# Power_2019_2.net
KiCad netlist of a schematic drawn in EAGLE
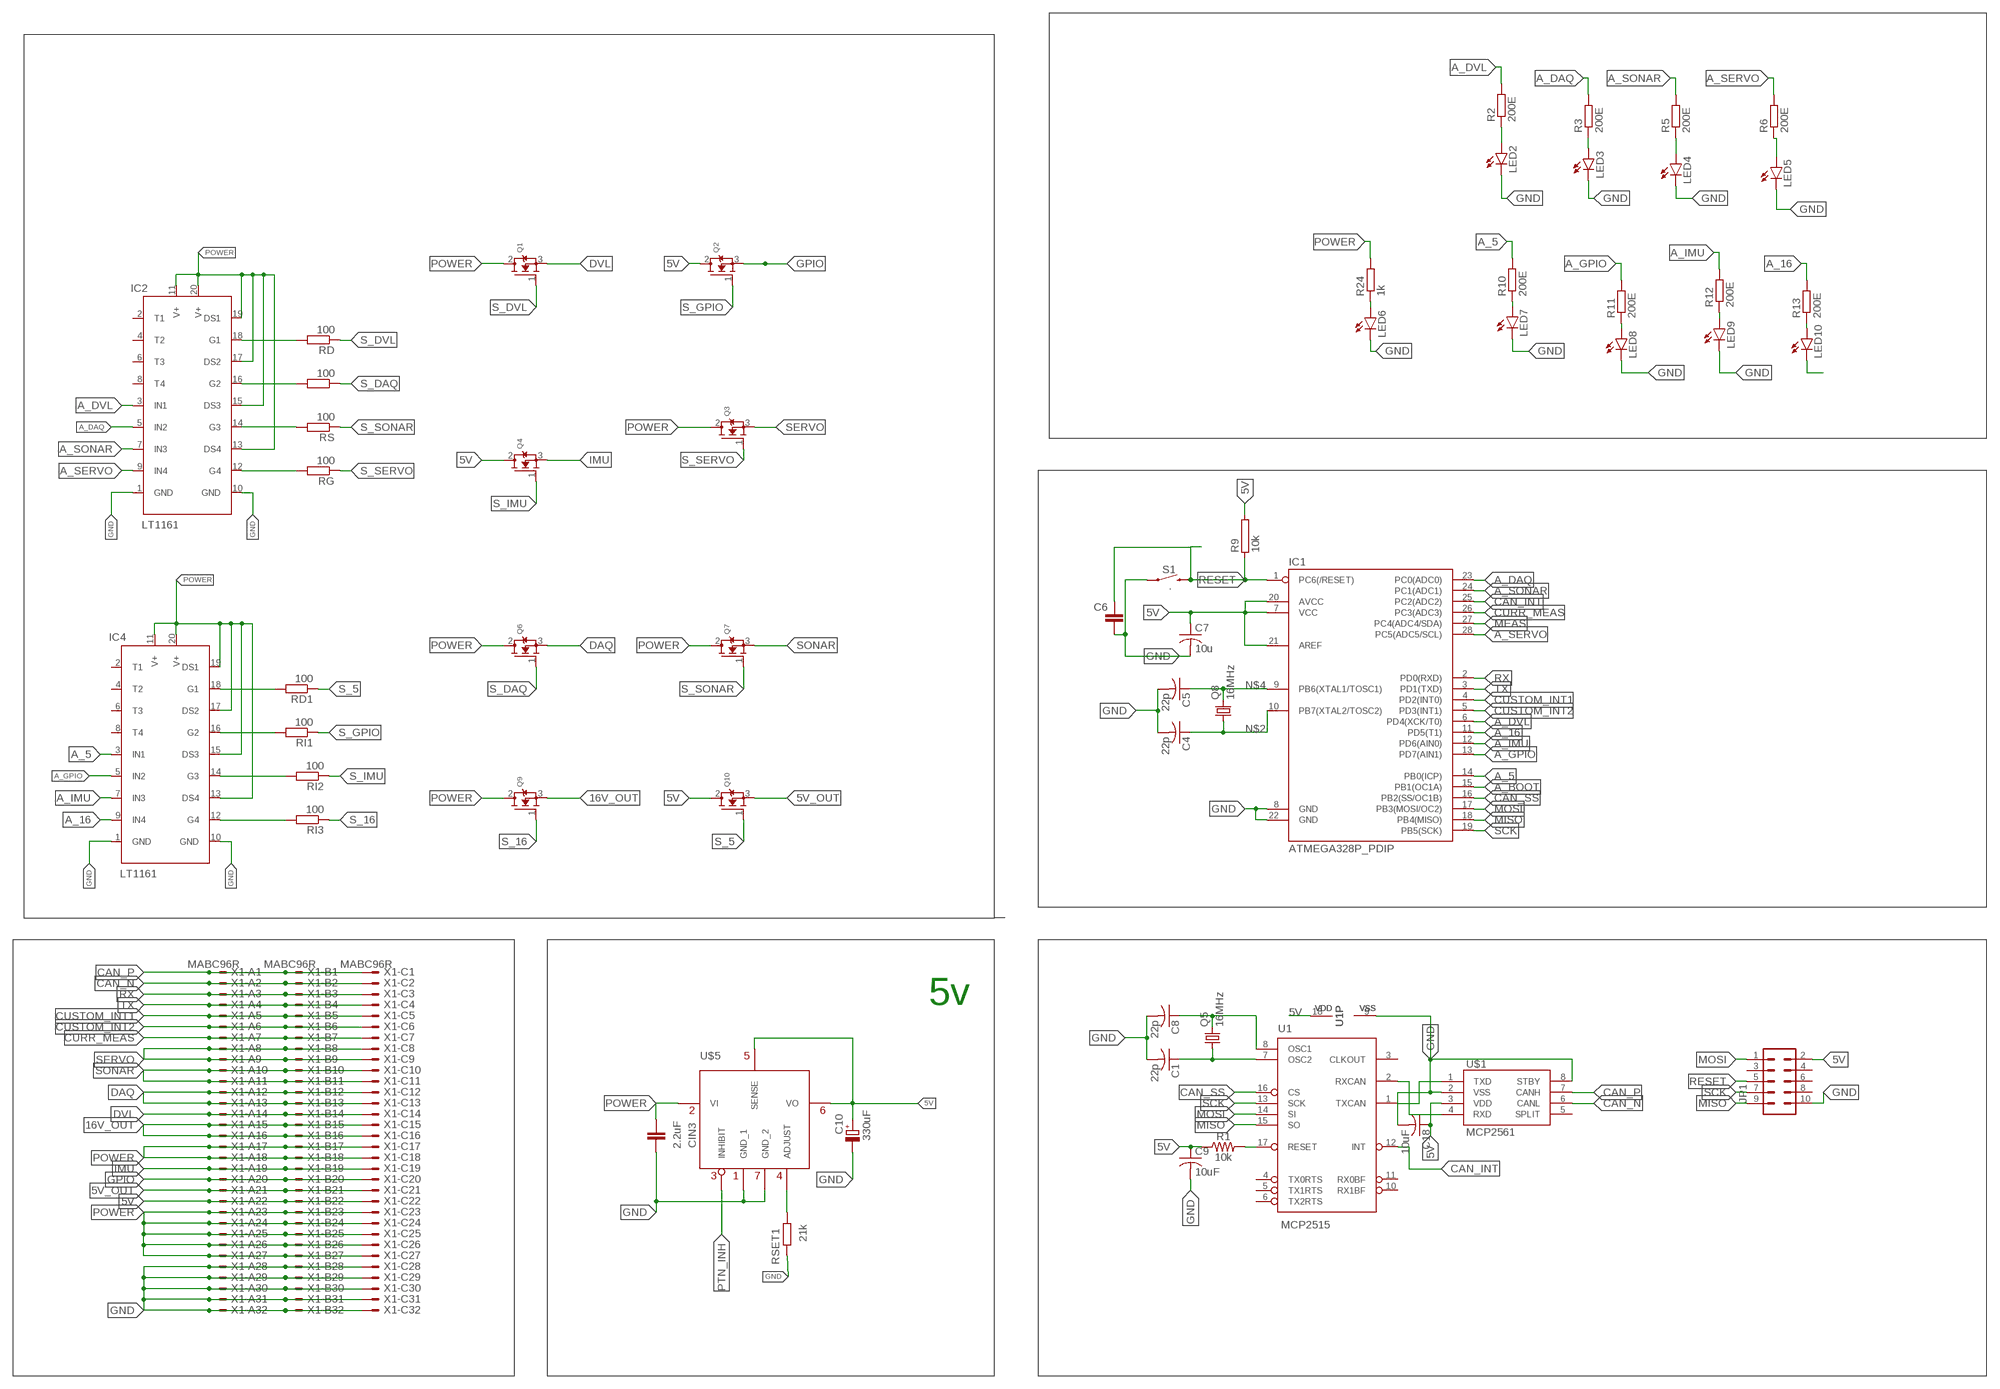
[diagram p0: schematic, sheet 1]

(export (version "E")
  (design (tool "Eeschema 10.0.6"))
  (components
    (comp (ref "C1")
      (value "22p")
      (footprint "eagle-import:C025-024X044")
      (libsource (lib "eagle-import") (part "resistor_C-US025-024X044"))
    )
    (comp (ref "C4")
      (value "22p")
      (footprint "eagle-import:C025-024X044")
      (libsource (lib "eagle-import") (part "resistor_C-US025-024X044"))
    )
    (comp (ref "C5")
      (value "22p")
      (footprint "eagle-import:C025-024X044")
      (libsource (lib "eagle-import") (part "resistor_C-US025-024X044"))
    )
    (comp (ref "C6")
      (value "C-EU025-050X050")
      (footprint "eagle-import:C025-050X050")
      (libsource (lib "eagle-import") (part "C-EU025-050X050"))
    )
    (comp (ref "C7")
      (value "10u")
      (footprint "eagle-import:C025-050X050")
      (libsource (lib "eagle-import") (part "resistor_C-US025-050X050"))
    )
    (comp (ref "C8")
      (value "22p")
      (footprint "eagle-import:C025-024X044")
      (libsource (lib "eagle-import") (part "resistor_C-US025-024X044"))
    )
    (comp (ref "C9")
      (value "10uF")
      (footprint "eagle-import:C025-050X050")
      (libsource (lib "eagle-import") (part "C-US025-050X050"))
    )
    (comp (ref "C10")
      (value "330uF")
      (footprint "eagle-import:E2,5-5")
      (libsource (lib "eagle-import") (part "CPOL-EUE2.5-5"))
    )
    (comp (ref "C18")
      (value "10uF")
      (footprint "eagle-import:C025-050X050")
      (libsource (lib "eagle-import") (part "C-US025-050X050"))
    )
    (comp (ref "CIN3")
      (value "2.2uF")
      (footprint "eagle-import:C0805")
      (libsource (lib "eagle-import") (part "C-EUC0805"))
    )
    (comp (ref "IC1")
      (value "ATMEGA328P_PDIP")
      (footprint "eagle-import:DIL28-3")
      (libsource (lib "eagle-import") (part "ATMEGA328P_PDIP"))
    )
    (comp (ref "IC2")
      (value "LT1161")
      (footprint "eagle-import:ROBOSUB_LINEAR-TECHNOLOGY_LT1161_QUAD-HIGH-SIDE-MOSFET-DRIVER_SO20")
      (fields (field (name "MF") "INTERSIL") (field (name "MPN") "HIP4086ABZ"))
      (libsource (lib "eagle-import") (part "ROBOSUB_LINEAR-TECHNOLOGY_LT1161_QUAD-HIGH-SIDE-MOSFET-DRIVER_LT1161-SO20SW"))
    )
    (comp (ref "IC4")
      (value "LT1161")
      (footprint "eagle-import:ROBOSUB_LINEAR-TECHNOLOGY_LT1161_QUAD-HIGH-SIDE-MOSFET-DRIVER_SO20")
      (fields (field (name "MF") "INTERSIL") (field (name "MPN") "HIP4086ABZ"))
      (libsource (lib "eagle-import") (part "ROBOSUB_LINEAR-TECHNOLOGY_LT1161_QUAD-HIGH-SIDE-MOSFET-DRIVER_LT1161-SO20SW"))
    )
    (comp (ref "JP1")
      (value "CONN_05X2SHD")
      (footprint "eagle-import:2X5-SHROUDED")
      (libsource (lib "eagle-import") (part "CONN_05X2SHD"))
    )
    (comp (ref "LED2")
      (value "LEDCHIPLED_0805")
      (footprint "eagle-import:CHIPLED_0805")
      (libsource (lib "eagle-import") (part "LEDCHIPLED_0805"))
    )
    (comp (ref "LED3")
      (value "LEDCHIPLED_0805")
      (footprint "eagle-import:CHIPLED_0805")
      (libsource (lib "eagle-import") (part "LEDCHIPLED_0805"))
    )
    (comp (ref "LED4")
      (value "LEDCHIPLED_0805")
      (footprint "eagle-import:CHIPLED_0805")
      (libsource (lib "eagle-import") (part "LEDCHIPLED_0805"))
    )
    (comp (ref "LED5")
      (value "LEDCHIPLED_0805")
      (footprint "eagle-import:CHIPLED_0805")
      (libsource (lib "eagle-import") (part "LEDCHIPLED_0805"))
    )
    (comp (ref "LED6")
      (value "LEDCHIPLED_0805")
      (footprint "eagle-import:CHIPLED_0805")
      (libsource (lib "eagle-import") (part "LEDCHIPLED_0805"))
    )
    (comp (ref "LED7")
      (value "LEDCHIPLED_0805")
      (footprint "eagle-import:CHIPLED_0805")
      (libsource (lib "eagle-import") (part "LEDCHIPLED_0805"))
    )
    (comp (ref "LED8")
      (value "LEDCHIPLED_0805")
      (footprint "eagle-import:CHIPLED_0805")
      (libsource (lib "eagle-import") (part "LEDCHIPLED_0805"))
    )
    (comp (ref "LED9")
      (value "LEDCHIPLED_0805")
      (footprint "eagle-import:CHIPLED_0805")
      (libsource (lib "eagle-import") (part "LEDCHIPLED_0805"))
    )
    (comp (ref "LED10")
      (value "LEDCHIPLED_0805")
      (footprint "eagle-import:CHIPLED_0805")
      (libsource (lib "eagle-import") (part "LEDCHIPLED_0805"))
    )
    (comp (ref "Q1")
      (value "MOSFET-NGDS_TO220V")
      (footprint "eagle-import:TO220V")
      (libsource (lib "eagle-import") (part "MOSFET-NGDS_TO220V"))
    )
    (comp (ref "Q2")
      (value "MOSFET-NGDS_TO220V")
      (footprint "eagle-import:TO220V")
      (libsource (lib "eagle-import") (part "MOSFET-NGDS_TO220V"))
    )
    (comp (ref "Q3")
      (value "MOSFET-NGDS_TO220V")
      (footprint "eagle-import:TO220V")
      (libsource (lib "eagle-import") (part "MOSFET-NGDS_TO220V"))
    )
    (comp (ref "Q4")
      (value "MOSFET-NGDS_TO220V")
      (footprint "eagle-import:TO220V")
      (libsource (lib "eagle-import") (part "MOSFET-NGDS_TO220V"))
    )
    (comp (ref "Q5")
      (value "16MHz")
      (footprint "eagle-import:HC49_S")
      (libsource (lib "eagle-import") (part "CRYSTALHC49S"))
    )
    (comp (ref "Q6")
      (value "MOSFET-NGDS_TO220V")
      (footprint "eagle-import:TO220V")
      (libsource (lib "eagle-import") (part "MOSFET-NGDS_TO220V"))
    )
    (comp (ref "Q7")
      (value "MOSFET-NGDS_TO220V")
      (footprint "eagle-import:TO220V")
      (libsource (lib "eagle-import") (part "MOSFET-NGDS_TO220V"))
    )
    (comp (ref "Q8")
      (value "16MHz")
      (footprint "eagle-import:HC49_S")
      (libsource (lib "eagle-import") (part "CRYSTALHC49S"))
    )
    (comp (ref "Q9")
      (value "MOSFET-NGDS_TO220V")
      (footprint "eagle-import:TO220V")
      (libsource (lib "eagle-import") (part "MOSFET-NGDS_TO220V"))
    )
    (comp (ref "Q10")
      (value "MOSFET-NGDS_TO220V")
      (footprint "eagle-import:TO220V")
      (libsource (lib "eagle-import") (part "MOSFET-NGDS_TO220V"))
    )
    (comp (ref "R1")
      (value "10k")
      (footprint "eagle-import:AXIAL-0.3")
      (libsource (lib "eagle-import") (part "RESISTORAXIAL-0.3"))
    )
    (comp (ref "R2")
      (value "200E")
      (footprint "eagle-import:M0805")
      (libsource (lib "eagle-import") (part "R-EU_M0805"))
    )
    (comp (ref "R3")
      (value "200E")
      (footprint "eagle-import:M0805")
      (libsource (lib "eagle-import") (part "R-EU_M0805"))
    )
    (comp (ref "R5")
      (value "200E")
      (footprint "eagle-import:M0805")
      (libsource (lib "eagle-import") (part "R-EU_M0805"))
    )
    (comp (ref "R6")
      (value "200E")
      (footprint "eagle-import:M0805")
      (libsource (lib "eagle-import") (part "R-EU_M0805"))
    )
    (comp (ref "R9")
      (value "10k")
      (footprint "eagle-import:RS1_4")
      (fields (field (name "MF") "OHMITE") (field (name "MPN") "RRS1K0"))
      (libsource (lib "eagle-import") (part "RRS1/4"))
    )
    (comp (ref "R10")
      (value "200E")
      (footprint "eagle-import:M0805")
      (libsource (lib "eagle-import") (part "R-EU_M0805"))
    )
    (comp (ref "R11")
      (value "200E")
      (footprint "eagle-import:M0805")
      (libsource (lib "eagle-import") (part "R-EU_M0805"))
    )
    (comp (ref "R12")
      (value "200E")
      (footprint "eagle-import:M0805")
      (libsource (lib "eagle-import") (part "R-EU_M0805"))
    )
    (comp (ref "R13")
      (value "200E")
      (footprint "eagle-import:M0805")
      (libsource (lib "eagle-import") (part "R-EU_M0805"))
    )
    (comp (ref "R24")
      (value "1k")
      (footprint "eagle-import:M0805")
      (libsource (lib "eagle-import") (part "R-EU_M0805"))
    )
    (comp (ref "RD")
      (value "100")
      (footprint "eagle-import:M0805")
      (libsource (lib "eagle-import") (part "R-EU_M0805"))
    )
    (comp (ref "RD1")
      (value "100")
      (footprint "eagle-import:M0805")
      (libsource (lib "eagle-import") (part "R-EU_M0805"))
    )
    (comp (ref "RG")
      (value "100")
      (footprint "eagle-import:M0805")
      (libsource (lib "eagle-import") (part "R-EU_M0805"))
    )
    (comp (ref "RI")
      (value "100")
      (footprint "eagle-import:M0805")
      (libsource (lib "eagle-import") (part "R-EU_M0805"))
    )
    (comp (ref "RI1")
      (value "100")
      (footprint "eagle-import:M0805")
      (libsource (lib "eagle-import") (part "R-EU_M0805"))
    )
    (comp (ref "RI2")
      (value "100")
      (footprint "eagle-import:M0805")
      (libsource (lib "eagle-import") (part "R-EU_M0805"))
    )
    (comp (ref "RI3")
      (value "100")
      (footprint "eagle-import:M0805")
      (libsource (lib "eagle-import") (part "R-EU_M0805"))
    )
    (comp (ref "RS")
      (value "100")
      (footprint "eagle-import:M0805")
      (libsource (lib "eagle-import") (part "R-EU_M0805"))
    )
    (comp (ref "RSET1")
      (value "21k")
      (footprint "eagle-import:M0805")
      (libsource (lib "eagle-import") (part "R-EU_M0805"))
    )
    (comp (ref "S1")
      (value ".")
      (footprint "eagle-import:TACTILE_SWITCH_PTH_6.0MM")
      (libsource (lib "eagle-import") (part "MOMENTARY-SWITCH-SPST-PTH-6.0MM"))
    )
    (comp (ref "U$1")
      (value "MCP2561")
      (footprint "eagle-import:DIP08")
      (libsource (lib "eagle-import") (part "MCP2561"))
    )
    (comp (ref "U$5")
      (value "PTN78060WAH")
      (footprint "eagle-import:PTN78060WAH")
      (libsource (lib "eagle-import") (part "PTN78060WAH"))
    )
    (comp (ref "U1")
      (value "MCP2515")
      (footprint "eagle-import:DIP18")
      (libsource (lib "eagle-import") (part "MCP2515(MCP2510)P"))
    )
    (comp (ref "X1")
      (value "MABC96R")
      (footprint "eagle-import:MABC96R")
      (fields (field (name "OC_FARNELL") "unknown"))
      (libsource (lib "eagle-import") (part "MABC96R"))
    )
  )
  (nets
    (net (code "1") (name "/N$2") (class "Default")
      (node (ref "C4") (pin "1") (pinfunction "1_1") (pintype "passive"))
      (node (ref "IC1") (pin "10") (pinfunction "PB7(XTAL2/TOSC2)_10") (pintype "bidirectional"))
      (node (ref "Q8") (pin "1") (pinfunction "1_1") (pintype "passive"))
    )
    (net (code "2") (name "/N$4") (class "Default")
      (node (ref "C5") (pin "1") (pinfunction "1_1") (pintype "passive"))
      (node (ref "IC1") (pin "9") (pinfunction "PB6(XTAL1/TOSC1)_9") (pintype "bidirectional"))
      (node (ref "Q8") (pin "2") (pinfunction "2_2") (pintype "passive"))
    )
    (net (code "3") (name "5V") (class "Default")
      (node (ref "C10") (pin "+") (pinfunction "+_+") (pintype "passive"))
      (node (ref "C18") (pin "1") (pinfunction "1_1") (pintype "passive"))
      (node (ref "C7") (pin "1") (pinfunction "1_1") (pintype "passive"))
      (node (ref "C9") (pin "1") (pinfunction "1_1") (pintype "passive"))
      (node (ref "IC1") (pin "20") (pinfunction "AVCC_20") (pintype "bidirectional"))
      (node (ref "IC1") (pin "21") (pinfunction "AREF_21") (pintype "bidirectional"))
      (node (ref "IC1") (pin "7") (pinfunction "VCC_7") (pintype "bidirectional"))
      (node (ref "JP1") (pin "2") (pinfunction "2_2") (pintype "passive"))
      (node (ref "Q10") (pin "2") (pinfunction "D_2") (pintype "bidirectional"))
      (node (ref "Q2") (pin "2") (pinfunction "D_2") (pintype "bidirectional"))
      (node (ref "Q4") (pin "2") (pinfunction "D_2") (pintype "bidirectional"))
      (node (ref "R1") (pin "P$1") (pinfunction "1_P$1") (pintype "passive"))
      (node (ref "R9") (pin "2") (pinfunction "2_2") (pintype "passive"))
      (node (ref "U$1") (pin "3") (pinfunction "VDD_3") (pintype "bidirectional"))
      (node (ref "U$5") (pin "5") (pinfunction "SENSE_5") (pintype "bidirectional"))
      (node (ref "U$5") (pin "6") (pinfunction "VO_6") (pintype "bidirectional"))
      (node (ref "U1") (pin "18") (pinfunction "VDD_18") (pintype "power_in"))
      (node (ref "X1") (pin "A22") (pinfunction "S_A22") (pintype "passive"))
      (node (ref "X1") (pin "B22") (pinfunction "S_B22") (pintype "passive"))
      (node (ref "X1") (pin "C22") (pinfunction "S_C22") (pintype "passive"))
    )
    (net (code "4") (name "5V_OUT") (class "Default")
      (node (ref "Q10") (pin "3") (pinfunction "S_3") (pintype "bidirectional"))
      (node (ref "X1") (pin "A21") (pinfunction "S_A21") (pintype "passive"))
      (node (ref "X1") (pin "B21") (pinfunction "S_B21") (pintype "passive"))
      (node (ref "X1") (pin "C21") (pinfunction "S_C21") (pintype "passive"))
    )
    (net (code "5") (name "16V_OUT") (class "Default")
      (node (ref "Q9") (pin "3") (pinfunction "S_3") (pintype "bidirectional"))
      (node (ref "X1") (pin "A15") (pinfunction "S_A15") (pintype "passive"))
      (node (ref "X1") (pin "A16") (pinfunction "S_A16") (pintype "passive"))
      (node (ref "X1") (pin "B15") (pinfunction "S_B15") (pintype "passive"))
      (node (ref "X1") (pin "B16") (pinfunction "S_B16") (pintype "passive"))
      (node (ref "X1") (pin "C15") (pinfunction "S_C15") (pintype "passive"))
      (node (ref "X1") (pin "C16") (pinfunction "S_C16") (pintype "passive"))
    )
    (net (code "6") (name "A_5") (class "Default")
      (node (ref "IC1") (pin "14") (pinfunction "PB0(ICP)_14") (pintype "bidirectional"))
      (node (ref "IC4") (pin "3") (pinfunction "IN1_3") (pintype "bidirectional"))
      (node (ref "R10") (pin "2") (pinfunction "2_2") (pintype "passive"))
    )
    (net (code "7") (name "A_16") (class "Default")
      (node (ref "IC1") (pin "11") (pinfunction "PD5(T1)_11") (pintype "bidirectional"))
      (node (ref "IC4") (pin "9") (pinfunction "IN4_9") (pintype "input"))
      (node (ref "R13") (pin "2") (pinfunction "2_2") (pintype "passive"))
    )
    (net (code "8") (name "A_BOOT") (class "Default")
      (node (ref "IC1") (pin "15") (pinfunction "PB1(OC1A)_15") (pintype "bidirectional"))
    )
    (net (code "9") (name "A_DAQ") (class "Default")
      (node (ref "IC1") (pin "23") (pinfunction "PC0(ADC0)_23") (pintype "bidirectional"))
      (node (ref "IC2") (pin "5") (pinfunction "IN2_5") (pintype "input"))
      (node (ref "R3") (pin "2") (pinfunction "2_2") (pintype "passive"))
    )
    (net (code "10") (name "A_DVL") (class "Default")
      (node (ref "IC1") (pin "6") (pinfunction "PD4(XCK/T0)_6") (pintype "bidirectional"))
      (node (ref "IC2") (pin "3") (pinfunction "IN1_3") (pintype "bidirectional"))
      (node (ref "R2") (pin "2") (pinfunction "2_2") (pintype "passive"))
    )
    (net (code "11") (name "A_GPIO") (class "Default")
      (node (ref "IC1") (pin "13") (pinfunction "PD7(AIN1)_13") (pintype "bidirectional"))
      (node (ref "IC4") (pin "5") (pinfunction "IN2_5") (pintype "input"))
      (node (ref "R11") (pin "2") (pinfunction "2_2") (pintype "passive"))
    )
    (net (code "12") (name "A_IMU") (class "Default")
      (node (ref "IC1") (pin "12") (pinfunction "PD6(AIN0)_12") (pintype "bidirectional"))
      (node (ref "IC4") (pin "7") (pinfunction "IN3_7") (pintype "input"))
      (node (ref "R12") (pin "2") (pinfunction "2_2") (pintype "passive"))
    )
    (net (code "13") (name "A_SERVO") (class "Default")
      (node (ref "IC1") (pin "28") (pinfunction "PC5(ADC5/SCL)_28") (pintype "bidirectional"))
      (node (ref "IC2") (pin "9") (pinfunction "IN4_9") (pintype "input"))
      (node (ref "R6") (pin "2") (pinfunction "2_2") (pintype "passive"))
    )
    (net (code "14") (name "A_SONAR") (class "Default")
      (node (ref "IC1") (pin "24") (pinfunction "PC1(ADC1)_24") (pintype "bidirectional"))
      (node (ref "IC2") (pin "7") (pinfunction "IN3_7") (pintype "input"))
      (node (ref "R5") (pin "2") (pinfunction "2_2") (pintype "passive"))
    )
    (net (code "15") (name "CAN_INT") (class "Default")
      (node (ref "IC1") (pin "25") (pinfunction "PC2(ADC2)_25") (pintype "bidirectional"))
      (node (ref "U1") (pin "12") (pinfunction "INT_12") (pintype "output"))
    )
    (net (code "16") (name "CAN_N") (class "Default")
      (node (ref "U$1") (pin "6") (pinfunction "CANL_6") (pintype "bidirectional"))
      (node (ref "X1") (pin "A2") (pinfunction "S_A2") (pintype "passive"))
      (node (ref "X1") (pin "B2") (pinfunction "S_B2") (pintype "passive"))
      (node (ref "X1") (pin "C2") (pinfunction "S_C2") (pintype "passive"))
    )
    (net (code "17") (name "CAN_P") (class "Default")
      (node (ref "U$1") (pin "7") (pinfunction "CANH_7") (pintype "bidirectional"))
      (node (ref "X1") (pin "A1") (pinfunction "S_A1") (pintype "passive"))
      (node (ref "X1") (pin "B1") (pinfunction "S_B1") (pintype "passive"))
      (node (ref "X1") (pin "C1") (pinfunction "S_C1") (pintype "passive"))
    )
    (net (code "18") (name "CAN_SS") (class "Default")
      (node (ref "IC1") (pin "16") (pinfunction "PB2(SS/OC1B)_16") (pintype "bidirectional"))
      (node (ref "U1") (pin "16") (pinfunction "CS_16") (pintype "input"))
    )
    (net (code "19") (name "CURR_MEAS") (class "Default")
      (node (ref "IC1") (pin "26") (pinfunction "PC3(ADC3)_26") (pintype "bidirectional"))
      (node (ref "X1") (pin "A7") (pinfunction "S_A7") (pintype "passive"))
      (node (ref "X1") (pin "B7") (pinfunction "S_B7") (pintype "passive"))
      (node (ref "X1") (pin "C7") (pinfunction "S_C7") (pintype "passive"))
    )
    (net (code "20") (name "CUSTOM_INT1") (class "Default")
      (node (ref "IC1") (pin "4") (pinfunction "PD2(INT0)_4") (pintype "bidirectional"))
      (node (ref "X1") (pin "A5") (pinfunction "S_A5") (pintype "passive"))
      (node (ref "X1") (pin "B5") (pinfunction "S_B5") (pintype "passive"))
      (node (ref "X1") (pin "C5") (pinfunction "S_C5") (pintype "passive"))
    )
    (net (code "21") (name "CUSTOM_INT2") (class "Default")
      (node (ref "IC1") (pin "5") (pinfunction "PD3(INT1)_5") (pintype "bidirectional"))
      (node (ref "X1") (pin "A6") (pinfunction "S_A6") (pintype "passive"))
      (node (ref "X1") (pin "B6") (pinfunction "S_B6") (pintype "passive"))
      (node (ref "X1") (pin "C6") (pinfunction "S_C6") (pintype "passive"))
    )
    (net (code "22") (name "DAQ") (class "Default")
      (node (ref "Q6") (pin "3") (pinfunction "S_3") (pintype "bidirectional"))
      (node (ref "X1") (pin "A12") (pinfunction "S_A12") (pintype "passive"))
      (node (ref "X1") (pin "A13") (pinfunction "S_A13") (pintype "passive"))
      (node (ref "X1") (pin "B12") (pinfunction "S_B12") (pintype "passive"))
      (node (ref "X1") (pin "B13") (pinfunction "S_B13") (pintype "passive"))
      (node (ref "X1") (pin "C12") (pinfunction "S_C12") (pintype "passive"))
      (node (ref "X1") (pin "C13") (pinfunction "S_C13") (pintype "passive"))
    )
    (net (code "23") (name "DVL") (class "Default")
      (node (ref "Q1") (pin "3") (pinfunction "S_3") (pintype "bidirectional"))
      (node (ref "X1") (pin "A14") (pinfunction "S_A14") (pintype "passive"))
      (node (ref "X1") (pin "B14") (pinfunction "S_B14") (pintype "passive"))
      (node (ref "X1") (pin "C14") (pinfunction "S_C14") (pintype "passive"))
    )
    (net (code "24") (name "GND") (class "Default")
      (node (ref "C1") (pin "2") (pinfunction "2_2") (pintype "passive"))
      (node (ref "C10") (pin "-") (pinfunction "-_-") (pintype "passive"))
      (node (ref "C18") (pin "2") (pinfunction "2_2") (pintype "passive"))
      (node (ref "C4") (pin "2") (pinfunction "2_2") (pintype "passive"))
      (node (ref "C5") (pin "2") (pinfunction "2_2") (pintype "passive"))
      (node (ref "C6") (pin "2") (pinfunction "2_2") (pintype "passive"))
      (node (ref "C7") (pin "2") (pinfunction "2_2") (pintype "passive"))
      (node (ref "C8") (pin "2") (pinfunction "2_2") (pintype "passive"))
      (node (ref "C9") (pin "2") (pinfunction "2_2") (pintype "passive"))
      (node (ref "CIN3") (pin "1") (pinfunction "1_1") (pintype "passive"))
      (node (ref "IC1") (pin "22") (pinfunction "GND_22") (pintype "bidirectional"))
      (node (ref "IC1") (pin "8") (pinfunction "GND_8") (pintype "bidirectional"))
      (node (ref "IC2") (pin "1") (pinfunction "GND_1") (pintype "power_in"))
      (node (ref "IC2") (pin "10") (pinfunction "GND_10") (pintype "power_in"))
      (node (ref "IC4") (pin "1") (pinfunction "GND_1") (pintype "power_in"))
      (node (ref "IC4") (pin "10") (pinfunction "GND_10") (pintype "power_in"))
      (node (ref "JP1") (pin "10") (pinfunction "10_10") (pintype "passive"))
      (node (ref "LED10") (pin "C") (pinfunction "C_C") (pintype "passive"))
      (node (ref "LED2") (pin "C") (pinfunction "C_C") (pintype "passive"))
      (node (ref "LED3") (pin "C") (pinfunction "C_C") (pintype "passive"))
      (node (ref "LED4") (pin "C") (pinfunction "C_C") (pintype "passive"))
      (node (ref "LED5") (pin "C") (pinfunction "C_C") (pintype "passive"))
      (node (ref "LED6") (pin "C") (pinfunction "C_C") (pintype "passive"))
      (node (ref "LED7") (pin "C") (pinfunction "C_C") (pintype "passive"))
      (node (ref "LED8") (pin "C") (pinfunction "C_C") (pintype "passive"))
      (node (ref "LED9") (pin "C") (pinfunction "C_C") (pintype "passive"))
      (node (ref "RSET1") (pin "2") (pinfunction "2_2") (pintype "passive"))
      (node (ref "S1") (pin "1") (pinfunction "1_1") (pintype "passive"))
      (node (ref "U$1") (pin "2") (pinfunction "VSS_2") (pintype "bidirectional"))
      (node (ref "U$1") (pin "8") (pinfunction "STBY_8") (pintype "bidirectional"))
      (node (ref "U$5") (pin "1") (pinfunction "GND_1_1") (pintype "bidirectional"))
      (node (ref "U$5") (pin "7") (pinfunction "GND_2_7") (pintype "bidirectional"))
      (node (ref "U1") (pin "9") (pinfunction "VSS_9") (pintype "power_in"))
      (node (ref "X1") (pin "A28") (pinfunction "S_A28") (pintype "passive"))
      (node (ref "X1") (pin "A29") (pinfunction "S_A29") (pintype "passive"))
      (node (ref "X1") (pin "A30") (pinfunction "S_A30") (pintype "passive"))
      (node (ref "X1") (pin "A31") (pinfunction "S_A31") (pintype "passive"))
      (node (ref "X1") (pin "A32") (pinfunction "S_A32") (pintype "passive"))
      (node (ref "X1") (pin "B28") (pinfunction "S_B28") (pintype "passive"))
      (node (ref "X1") (pin "B29") (pinfunction "S_B29") (pintype "passive"))
      (node (ref "X1") (pin "B30") (pinfunction "S_B30") (pintype "passive"))
      (node (ref "X1") (pin "B31") (pinfunction "S_B31") (pintype "passive"))
      (node (ref "X1") (pin "B32") (pinfunction "S_B32") (pintype "passive"))
      (node (ref "X1") (pin "C28") (pinfunction "S_C28") (pintype "passive"))
      (node (ref "X1") (pin "C29") (pinfunction "S_C29") (pintype "passive"))
      (node (ref "X1") (pin "C30") (pinfunction "S_C30") (pintype "passive"))
      (node (ref "X1") (pin "C31") (pinfunction "S_C31") (pintype "passive"))
      (node (ref "X1") (pin "C32") (pinfunction "S_C32") (pintype "passive"))
    )
    (net (code "25") (name "GPIO") (class "Default")
      (node (ref "Q2") (pin "3") (pinfunction "S_3") (pintype "bidirectional"))
      (node (ref "X1") (pin "A20") (pinfunction "S_A20") (pintype "passive"))
      (node (ref "X1") (pin "B20") (pinfunction "S_B20") (pintype "passive"))
      (node (ref "X1") (pin "C20") (pinfunction "S_C20") (pintype "passive"))
    )
    (net (code "26") (name "IMU") (class "Default")
      (node (ref "Q4") (pin "3") (pinfunction "S_3") (pintype "bidirectional"))
      (node (ref "X1") (pin "A19") (pinfunction "S_A19") (pintype "passive"))
      (node (ref "X1") (pin "B19") (pinfunction "S_B19") (pintype "passive"))
      (node (ref "X1") (pin "C19") (pinfunction "S_C19") (pintype "passive"))
    )
    (net (code "27") (name "MEAS") (class "Default")
      (node (ref "IC1") (pin "27") (pinfunction "PC4(ADC4/SDA)_27") (pintype "bidirectional"))
    )
    (net (code "28") (name "MISO") (class "Default")
      (node (ref "IC1") (pin "18") (pinfunction "PB4(MISO)_18") (pintype "bidirectional"))
      (node (ref "JP1") (pin "9") (pinfunction "9_9") (pintype "passive"))
      (node (ref "U1") (pin "15") (pinfunction "SO_15") (pintype "output"))
    )
    (net (code "29") (name "MOSI") (class "Default")
      (node (ref "IC1") (pin "17") (pinfunction "PB3(MOSI/OC2)_17") (pintype "bidirectional"))
      (node (ref "JP1") (pin "1") (pinfunction "1_1") (pintype "passive"))
      (node (ref "U1") (pin "14") (pinfunction "SI_14") (pintype "input"))
    )
    (net (code "30") (name "Net-(IC2-G1)") (class "Default")
      (node (ref "IC2") (pin "18") (pinfunction "G1_18") (pintype "output"))
      (node (ref "RD") (pin "2") (pinfunction "2_2") (pintype "passive"))
    )
    (net (code "31") (name "Net-(IC2-G2)") (class "Default")
      (node (ref "IC2") (pin "16") (pinfunction "G2_16") (pintype "output"))
      (node (ref "RI") (pin "2") (pinfunction "2_2") (pintype "passive"))
    )
    (net (code "32") (name "Net-(IC2-G3)") (class "Default")
      (node (ref "IC2") (pin "14") (pinfunction "G3_14") (pintype "output"))
      (node (ref "RS") (pin "2") (pinfunction "2_2") (pintype "passive"))
    )
    (net (code "33") (name "Net-(IC2-G4)") (class "Default")
      (node (ref "IC2") (pin "12") (pinfunction "G4_12") (pintype "output"))
      (node (ref "RG") (pin "2") (pinfunction "2_2") (pintype "passive"))
    )
    (net (code "34") (name "Net-(IC4-G1)") (class "Default")
      (node (ref "IC4") (pin "18") (pinfunction "G1_18") (pintype "output"))
      (node (ref "RD1") (pin "2") (pinfunction "2_2") (pintype "passive"))
    )
    (net (code "35") (name "Net-(IC4-G2)") (class "Default")
      (node (ref "IC4") (pin "16") (pinfunction "G2_16") (pintype "output"))
      (node (ref "RI1") (pin "2") (pinfunction "2_2") (pintype "passive"))
    )
    (net (code "36") (name "Net-(IC4-G3)") (class "Default")
      (node (ref "IC4") (pin "14") (pinfunction "G3_14") (pintype "output"))
      (node (ref "RI2") (pin "2") (pinfunction "2_2") (pintype "passive"))
    )
    (net (code "37") (name "Net-(IC4-G4)") (class "Default")
      (node (ref "IC4") (pin "12") (pinfunction "G4_12") (pintype "output"))
      (node (ref "RI3") (pin "2") (pinfunction "2_2") (pintype "passive"))
    )
    (net (code "38") (name "Net-(LED2-PadA)") (class "Default")
      (node (ref "LED2") (pin "A") (pinfunction "A_A") (pintype "passive"))
      (node (ref "R2") (pin "1") (pinfunction "1_1") (pintype "passive"))
    )
    (net (code "39") (name "Net-(LED3-PadA)") (class "Default")
      (node (ref "LED3") (pin "A") (pinfunction "A_A") (pintype "passive"))
      (node (ref "R3") (pin "1") (pinfunction "1_1") (pintype "passive"))
    )
    (net (code "40") (name "Net-(LED4-PadA)") (class "Default")
      (node (ref "LED4") (pin "A") (pinfunction "A_A") (pintype "passive"))
      (node (ref "R5") (pin "1") (pinfunction "1_1") (pintype "passive"))
    )
    (net (code "41") (name "Net-(LED5-PadA)") (class "Default")
      (node (ref "LED5") (pin "A") (pinfunction "A_A") (pintype "passive"))
      (node (ref "R6") (pin "1") (pinfunction "1_1") (pintype "passive"))
    )
    (net (code "42") (name "Net-(LED6-PadA)") (class "Default")
      (node (ref "LED6") (pin "A") (pinfunction "A_A") (pintype "passive"))
      (node (ref "R24") (pin "1") (pinfunction "1_1") (pintype "passive"))
    )
    (net (code "43") (name "Net-(LED7-PadA)") (class "Default")
      (node (ref "LED7") (pin "A") (pinfunction "A_A") (pintype "passive"))
      (node (ref "R10") (pin "1") (pinfunction "1_1") (pintype "passive"))
    )
    (net (code "44") (name "Net-(LED8-PadA)") (class "Default")
      (node (ref "LED8") (pin "A") (pinfunction "A_A") (pintype "passive"))
      (node (ref "R11") (pin "1") (pinfunction "1_1") (pintype "passive"))
    )
    (net (code "45") (name "Net-(LED9-PadA)") (class "Default")
      (node (ref "LED9") (pin "A") (pinfunction "A_A") (pintype "passive"))
      (node (ref "R12") (pin "1") (pinfunction "1_1") (pintype "passive"))
    )
    (net (code "46") (name "Net-(LED10-PadA)") (class "Default")
      (node (ref "LED10") (pin "A") (pinfunction "A_A") (pintype "passive"))
      (node (ref "R13") (pin "1") (pinfunction "1_1") (pintype "passive"))
    )
    (net (code "47") (name "Net-(R1-2)") (class "Default")
      (node (ref "R1") (pin "P$2") (pinfunction "2_P$2") (pintype "passive"))
      (node (ref "U1") (pin "17") (pinfunction "RESET_17") (pintype "input"))
    )
    (net (code "48") (name "Net-(U$1-RXD)") (class "Default")
      (node (ref "U$1") (pin "4") (pinfunction "RXD_4") (pintype "bidirectional"))
      (node (ref "U1") (pin "2") (pinfunction "RXCAN_2") (pintype "input"))
    )
    (net (code "49") (name "Net-(U$1-TXD)") (class "Default")
      (node (ref "U$1") (pin "1") (pinfunction "TXD_1") (pintype "bidirectional"))
      (node (ref "U1") (pin "1") (pinfunction "TXCAN_1") (pintype "output"))
    )
    (net (code "50") (name "Net-(U$5-ADJUST)") (class "Default")
      (node (ref "RSET1") (pin "1") (pinfunction "1_1") (pintype "passive"))
      (node (ref "U$5") (pin "4") (pinfunction "ADJUST_4") (pintype "bidirectional"))
    )
    (net (code "51") (name "Net-(U1A-OSC1)") (class "Default")
      (node (ref "C8") (pin "1") (pinfunction "1_1") (pintype "passive"))
      (node (ref "Q5") (pin "2") (pinfunction "2_2") (pintype "passive"))
      (node (ref "U1") (pin "8") (pinfunction "OSC1_8") (pintype "input"))
    )
    (net (code "52") (name "Net-(U1A-OSC2)") (class "Default")
      (node (ref "C1") (pin "1") (pinfunction "1_1") (pintype "passive"))
      (node (ref "Q5") (pin "1") (pinfunction "1_1") (pintype "passive"))
      (node (ref "U1") (pin "7") (pinfunction "OSC2_7") (pintype "output"))
    )
    (net (code "53") (name "POWER") (class "Default")
      (node (ref "CIN3") (pin "2") (pinfunction "2_2") (pintype "passive"))
      (node (ref "IC2") (pin "11") (pinfunction "V+_11") (pintype "power_in"))
      (node (ref "IC2") (pin "13") (pinfunction "DS4_13") (pintype "input"))
      (node (ref "IC2") (pin "15") (pinfunction "DS3_15") (pintype "input"))
      (node (ref "IC2") (pin "17") (pinfunction "DS2_17") (pintype "input"))
      (node (ref "IC2") (pin "19") (pinfunction "DS1_19") (pintype "input"))
      (node (ref "IC2") (pin "20") (pinfunction "V+_20") (pintype "power_in"))
      (node (ref "IC4") (pin "11") (pinfunction "V+_11") (pintype "power_in"))
      (node (ref "IC4") (pin "13") (pinfunction "DS4_13") (pintype "input"))
      (node (ref "IC4") (pin "15") (pinfunction "DS3_15") (pintype "input"))
      (node (ref "IC4") (pin "17") (pinfunction "DS2_17") (pintype "input"))
      (node (ref "IC4") (pin "19") (pinfunction "DS1_19") (pintype "input"))
      (node (ref "IC4") (pin "20") (pinfunction "V+_20") (pintype "power_in"))
      (node (ref "Q1") (pin "2") (pinfunction "D_2") (pintype "bidirectional"))
      (node (ref "Q3") (pin "2") (pinfunction "D_2") (pintype "bidirectional"))
      (node (ref "Q6") (pin "2") (pinfunction "D_2") (pintype "bidirectional"))
      (node (ref "Q7") (pin "2") (pinfunction "D_2") (pintype "bidirectional"))
      (node (ref "Q9") (pin "2") (pinfunction "D_2") (pintype "bidirectional"))
      (node (ref "R24") (pin "2") (pinfunction "2_2") (pintype "passive"))
      (node (ref "U$5") (pin "2") (pinfunction "VI_2") (pintype "bidirectional"))
      (node (ref "X1") (pin "A17") (pinfunction "S_A17") (pintype "passive"))
      (node (ref "X1") (pin "A18") (pinfunction "S_A18") (pintype "passive"))
      (node (ref "X1") (pin "A23") (pinfunction "S_A23") (pintype "passive"))
      (node (ref "X1") (pin "A24") (pinfunction "S_A24") (pintype "passive"))
      (node (ref "X1") (pin "A25") (pinfunction "S_A25") (pintype "passive"))
      (node (ref "X1") (pin "A26") (pinfunction "S_A26") (pintype "passive"))
      (node (ref "X1") (pin "A27") (pinfunction "S_A27") (pintype "passive"))
      (node (ref "X1") (pin "B17") (pinfunction "S_B17") (pintype "passive"))
      (node (ref "X1") (pin "B18") (pinfunction "S_B18") (pintype "passive"))
      (node (ref "X1") (pin "B23") (pinfunction "S_B23") (pintype "passive"))
      (node (ref "X1") (pin "B24") (pinfunction "S_B24") (pintype "passive"))
      (node (ref "X1") (pin "B25") (pinfunction "S_B25") (pintype "passive"))
      (node (ref "X1") (pin "B26") (pinfunction "S_B26") (pintype "passive"))
      (node (ref "X1") (pin "B27") (pinfunction "S_B27") (pintype "passive"))
      (node (ref "X1") (pin "C17") (pinfunction "S_C17") (pintype "passive"))
      (node (ref "X1") (pin "C18") (pinfunction "S_C18") (pintype "passive"))
      (node (ref "X1") (pin "C23") (pinfunction "S_C23") (pintype "passive"))
      (node (ref "X1") (pin "C24") (pinfunction "S_C24") (pintype "passive"))
      (node (ref "X1") (pin "C25") (pinfunction "S_C25") (pintype "passive"))
      (node (ref "X1") (pin "C26") (pinfunction "S_C26") (pintype "passive"))
      (node (ref "X1") (pin "C27") (pinfunction "S_C27") (pintype "passive"))
    )
    (net (code "54") (name "PTN_INH") (class "Default")
      (node (ref "U$5") (pin "3") (pinfunction "INHIBIT_3") (pintype "bidirectional"))
    )
    (net (code "55") (name "RESET") (class "Default")
      (node (ref "C6") (pin "1") (pinfunction "1_1") (pintype "passive"))
      (node (ref "IC1") (pin "1") (pinfunction "PC6(/RESET)_1") (pintype "bidirectional"))
      (node (ref "JP1") (pin "5") (pinfunction "5_5") (pintype "passive"))
      (node (ref "R9") (pin "1") (pinfunction "1_1") (pintype "passive"))
      (node (ref "S1") (pin "3") (pinfunction "2_3") (pintype "passive"))
    )
    (net (code "56") (name "RX") (class "Default")
      (node (ref "IC1") (pin "2") (pinfunction "PD0(RXD)_2") (pintype "bidirectional"))
      (node (ref "X1") (pin "A3") (pinfunction "S_A3") (pintype "passive"))
      (node (ref "X1") (pin "B3") (pinfunction "S_B3") (pintype "passive"))
      (node (ref "X1") (pin "C3") (pinfunction "S_C3") (pintype "passive"))
    )
    (net (code "57") (name "SCK") (class "Default")
      (node (ref "IC1") (pin "19") (pinfunction "PB5(SCK)_19") (pintype "bidirectional"))
      (node (ref "JP1") (pin "7") (pinfunction "7_7") (pintype "passive"))
      (node (ref "U1") (pin "13") (pinfunction "SCK_13") (pintype "input"))
    )
    (net (code "58") (name "SERVO") (class "Default")
      (node (ref "Q3") (pin "3") (pinfunction "S_3") (pintype "bidirectional"))
      (node (ref "X1") (pin "A8") (pinfunction "S_A8") (pintype "passive"))
      (node (ref "X1") (pin "A9") (pinfunction "S_A9") (pintype "passive"))
      (node (ref "X1") (pin "B8") (pinfunction "S_B8") (pintype "passive"))
      (node (ref "X1") (pin "B9") (pinfunction "S_B9") (pintype "passive"))
      (node (ref "X1") (pin "C8") (pinfunction "S_C8") (pintype "passive"))
      (node (ref "X1") (pin "C9") (pinfunction "S_C9") (pintype "passive"))
    )
    (net (code "59") (name "SONAR") (class "Default")
      (node (ref "Q7") (pin "3") (pinfunction "S_3") (pintype "bidirectional"))
      (node (ref "X1") (pin "A10") (pinfunction "S_A10") (pintype "passive"))
      (node (ref "X1") (pin "A11") (pinfunction "S_A11") (pintype "passive"))
      (node (ref "X1") (pin "B10") (pinfunction "S_B10") (pintype "passive"))
      (node (ref "X1") (pin "B11") (pinfunction "S_B11") (pintype "passive"))
      (node (ref "X1") (pin "C10") (pinfunction "S_C10") (pintype "passive"))
      (node (ref "X1") (pin "C11") (pinfunction "S_C11") (pintype "passive"))
    )
    (net (code "60") (name "S_5") (class "Default")
      (node (ref "Q10") (pin "1") (pinfunction "G_1") (pintype "bidirectional"))
      (node (ref "RD1") (pin "1") (pinfunction "1_1") (pintype "passive"))
    )
    (net (code "61") (name "S_16") (class "Default")
      (node (ref "Q9") (pin "1") (pinfunction "G_1") (pintype "bidirectional"))
      (node (ref "RI3") (pin "1") (pinfunction "1_1") (pintype "passive"))
    )
    (net (code "62") (name "S_DAQ") (class "Default")
      (node (ref "Q6") (pin "1") (pinfunction "G_1") (pintype "bidirectional"))
      (node (ref "RI") (pin "1") (pinfunction "1_1") (pintype "passive"))
    )
    (net (code "63") (name "S_DVL") (class "Default")
      (node (ref "Q1") (pin "1") (pinfunction "G_1") (pintype "bidirectional"))
      (node (ref "RD") (pin "1") (pinfunction "1_1") (pintype "passive"))
    )
    (net (code "64") (name "S_GPIO") (class "Default")
      (node (ref "Q2") (pin "1") (pinfunction "G_1") (pintype "bidirectional"))
      (node (ref "RI1") (pin "1") (pinfunction "1_1") (pintype "passive"))
    )
    (net (code "65") (name "S_IMU") (class "Default")
      (node (ref "Q4") (pin "1") (pinfunction "G_1") (pintype "bidirectional"))
      (node (ref "RI2") (pin "1") (pinfunction "1_1") (pintype "passive"))
    )
    (net (code "66") (name "S_SERVO") (class "Default")
      (node (ref "Q3") (pin "1") (pinfunction "G_1") (pintype "bidirectional"))
      (node (ref "RG") (pin "1") (pinfunction "1_1") (pintype "passive"))
    )
    (net (code "67") (name "S_SONAR") (class "Default")
      (node (ref "Q7") (pin "1") (pinfunction "G_1") (pintype "bidirectional"))
      (node (ref "RS") (pin "1") (pinfunction "1_1") (pintype "passive"))
    )
    (net (code "68") (name "TX") (class "Default")
      (node (ref "IC1") (pin "3") (pinfunction "PD1(TXD)_3") (pintype "bidirectional"))
      (node (ref "X1") (pin "A4") (pinfunction "S_A4") (pintype "passive"))
      (node (ref "X1") (pin "B4") (pinfunction "S_B4") (pintype "passive"))
      (node (ref "X1") (pin "C4") (pinfunction "S_C4") (pintype "passive"))
    )
    (net (code "69") (name "unconnected-(IC2-T1-Pad2)") (class "Default")
      (node (ref "IC2") (pin "2") (pinfunction "T1_2") (pintype "bidirectional"))
    )
    (net (code "70") (name "unconnected-(IC2-T2-Pad4)") (class "Default")
      (node (ref "IC2") (pin "4") (pinfunction "T2_4") (pintype "bidirectional"))
    )
    (net (code "71") (name "unconnected-(IC2-T3-Pad6)") (class "Default")
      (node (ref "IC2") (pin "6") (pinfunction "T3_6") (pintype "bidirectional"))
    )
    (net (code "72") (name "unconnected-(IC2-T4-Pad8)") (class "Default")
      (node (ref "IC2") (pin "8") (pinfunction "T4_8") (pintype "bidirectional"))
    )
    (net (code "73") (name "unconnected-(IC4-T1-Pad2)") (class "Default")
      (node (ref "IC4") (pin "2") (pinfunction "T1_2") (pintype "bidirectional"))
    )
    (net (code "74") (name "unconnected-(IC4-T2-Pad4)") (class "Default")
      (node (ref "IC4") (pin "4") (pinfunction "T2_4") (pintype "bidirectional"))
    )
    (net (code "75") (name "unconnected-(IC4-T3-Pad6)") (class "Default")
      (node (ref "IC4") (pin "6") (pinfunction "T3_6") (pintype "bidirectional"))
    )
    (net (code "76") (name "unconnected-(IC4-T4-Pad8)") (class "Default")
      (node (ref "IC4") (pin "8") (pinfunction "T4_8") (pintype "bidirectional"))
    )
    (net (code "77") (name "unconnected-(JP1-Pad3)") (class "Default")
      (node (ref "JP1") (pin "3") (pinfunction "3_3") (pintype "passive"))
    )
    (net (code "78") (name "unconnected-(JP1-Pad4)") (class "Default")
      (node (ref "JP1") (pin "4") (pinfunction "4_4") (pintype "passive"))
    )
    (net (code "79") (name "unconnected-(JP1-Pad6)") (class "Default")
      (node (ref "JP1") (pin "6") (pinfunction "6_6") (pintype "passive"))
    )
    (net (code "80") (name "unconnected-(JP1-Pad8)") (class "Default")
      (node (ref "JP1") (pin "8") (pinfunction "8_8") (pintype "passive"))
    )
    (net (code "81") (name "unconnected-(U$1-SPLIT-Pad5)") (class "Default")
      (node (ref "U$1") (pin "5") (pinfunction "SPLIT_5") (pintype "bidirectional"))
    )
    (net (code "82") (name "unconnected-(U1A-CLKOUT-Pad3)") (class "Default")
      (node (ref "U1") (pin "3") (pinfunction "CLKOUT_3") (pintype "output"))
    )
    (net (code "83") (name "unconnected-(U1A-RX0BF-Pad11)") (class "Default")
      (node (ref "U1") (pin "11") (pinfunction "RX0BF_11") (pintype "output"))
    )
    (net (code "84") (name "unconnected-(U1A-RX1BF-Pad10)") (class "Default")
      (node (ref "U1") (pin "10") (pinfunction "RX1BF_10") (pintype "output"))
    )
    (net (code "85") (name "unconnected-(U1A-TX0RTS-Pad4)") (class "Default")
      (node (ref "U1") (pin "4") (pinfunction "TX0RTS_4") (pintype "input"))
    )
    (net (code "86") (name "unconnected-(U1A-TX1RTS-Pad5)") (class "Default")
      (node (ref "U1") (pin "5") (pinfunction "TX1RTS_5") (pintype "input"))
    )
    (net (code "87") (name "unconnected-(U1A-TX2RTS-Pad6)") (class "Default")
      (node (ref "U1") (pin "6") (pinfunction "TX2RTS_6") (pintype "input"))
    )
  )
)
